# n64-snac.net
KiCad netlist of a schematic drawn in EAGLE
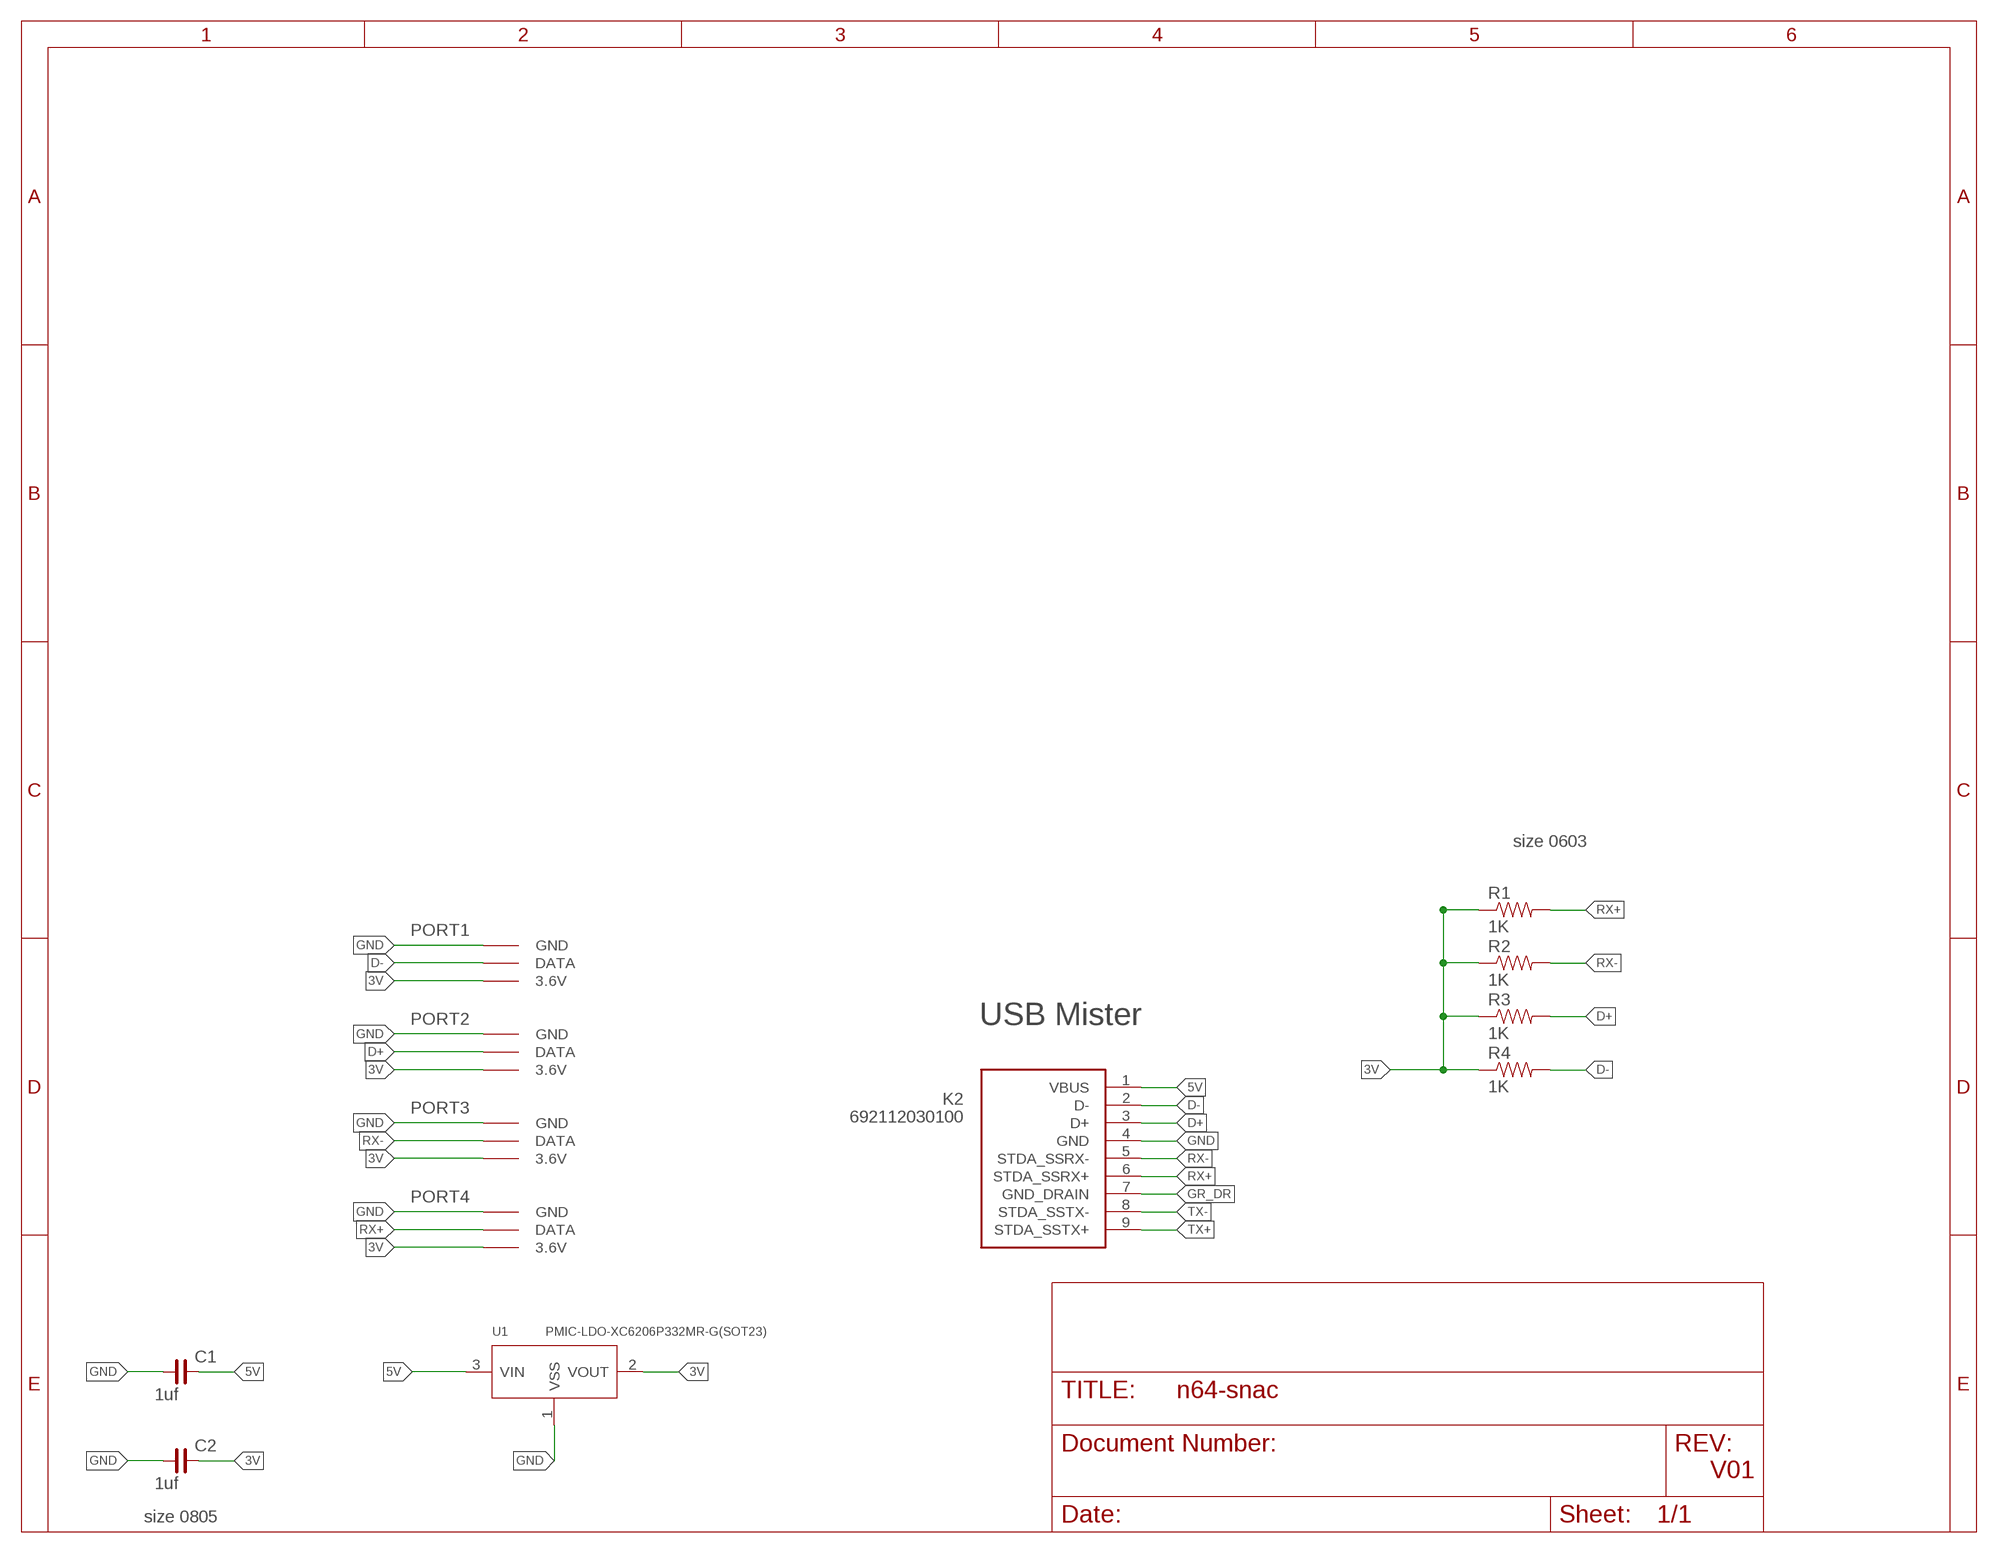
[diagram p0: schematic, sheet 1]

(export (version "E")
  (design (tool "Eeschema 10.0.6"))
  (components
    (comp (ref "C1")
      (value "1uf")
      (footprint "eagle-import:C0805")
      (libsource (lib "eagle-import") (part "C_0805"))
    )
    (comp (ref "C2")
      (value "1uf")
      (footprint "eagle-import:C0805")
      (libsource (lib "eagle-import") (part "C_0805"))
    )
    (comp (ref "K2")
      (value "692112030100")
      (footprint "eagle-import:692112030100")
      (libsource (lib "eagle-import") (part "692112030100"))
    )
    (comp (ref "R1")
      (value "1K")
      (footprint "eagle-import:0603-RES")
      (libsource (lib "eagle-import") (part "RESISTOR0603-RES"))
    )
    (comp (ref "R2")
      (value "1K")
      (footprint "eagle-import:0603-RES")
      (libsource (lib "eagle-import") (part "RESISTOR0603-RES"))
    )
    (comp (ref "R3")
      (value "1K")
      (footprint "eagle-import:0603-RES")
      (libsource (lib "eagle-import") (part "RESISTOR0603-RES"))
    )
    (comp (ref "R4")
      (value "1K")
      (footprint "eagle-import:0603-RES")
      (libsource (lib "eagle-import") (part "RESISTOR0603-RES"))
    )
    (comp (ref "U$1")
      (value "N64CONN")
      (footprint "eagle-import:N64CONN")
      (libsource (lib "eagle-import") (part "N64CONN"))
    )
    (comp (ref "U$2")
      (value "N64CONN")
      (footprint "eagle-import:N64CONN")
      (libsource (lib "eagle-import") (part "N64CONN"))
    )
    (comp (ref "U$3")
      (value "N64CONN")
      (footprint "eagle-import:N64CONN")
      (libsource (lib "eagle-import") (part "N64CONN"))
    )
    (comp (ref "U$4")
      (value "N64CONN")
      (footprint "eagle-import:N64CONN")
      (libsource (lib "eagle-import") (part "N64CONN"))
    )
    (comp (ref "U1")
      (value "PMIC-LDO-XC6206P332MR-G(SOT23)")
      (footprint "eagle-import:SOT-23")
      (fields (field (name "MF") "Torex") (field (name "MP") "XC6206P332MR-G"))
      (libsource (lib "eagle-import") (part "PMIC-LDO-XC6206P332MR-G(SOT23)"))
    )
  )
  (nets
    (net (code "1") (name "3V") (class "Default")
      (node (ref "C2") (pin "2") (pinfunction "2_2") (pintype "passive"))
      (node (ref "R1") (pin "1") (pinfunction "1_1") (pintype "passive"))
      (node (ref "R2") (pin "1") (pinfunction "1_1") (pintype "passive"))
      (node (ref "R3") (pin "1") (pinfunction "1_1") (pintype "passive"))
      (node (ref "R4") (pin "1") (pinfunction "1_1") (pintype "passive"))
      (node (ref "U$1") (pin "3.6V") (pinfunction "3.6V_3.6V") (pintype "power_in"))
      (node (ref "U$2") (pin "3.6V") (pinfunction "3.6V_3.6V") (pintype "power_in"))
      (node (ref "U$3") (pin "3.6V") (pinfunction "3.6V_3.6V") (pintype "power_in"))
      (node (ref "U$4") (pin "3.6V") (pinfunction "3.6V_3.6V") (pintype "power_in"))
      (node (ref "U1") (pin "2") (pinfunction "VOUT_2") (pintype "output"))
    )
    (net (code "2") (name "5V") (class "Default")
      (node (ref "C1") (pin "2") (pinfunction "2_2") (pintype "passive"))
      (node (ref "K2") (pin "1") (pinfunction "VBUS_1") (pintype "bidirectional"))
      (node (ref "U1") (pin "3") (pinfunction "VIN_3") (pintype "input"))
    )
    (net (code "3") (name "D+") (class "Default")
      (node (ref "K2") (pin "3") (pinfunction "D+_3") (pintype "bidirectional"))
      (node (ref "R3") (pin "2") (pinfunction "2_2") (pintype "passive"))
      (node (ref "U$1") (pin "DATA") (pinfunction "DATA_DATA") (pintype "bidirectional"))
    )
    (net (code "4") (name "D-") (class "Default")
      (node (ref "K2") (pin "2") (pinfunction "D-_2") (pintype "bidirectional"))
      (node (ref "R4") (pin "2") (pinfunction "2_2") (pintype "passive"))
      (node (ref "U$3") (pin "DATA") (pinfunction "DATA_DATA") (pintype "bidirectional"))
    )
    (net (code "5") (name "GND") (class "Default")
      (node (ref "C1") (pin "1") (pinfunction "1_1") (pintype "passive"))
      (node (ref "C2") (pin "1") (pinfunction "1_1") (pintype "passive"))
      (node (ref "K2") (pin "4") (pinfunction "GND_4") (pintype "bidirectional"))
      (node (ref "U$1") (pin "GND") (pinfunction "GND_GND") (pintype "input"))
      (node (ref "U$2") (pin "GND") (pinfunction "GND_GND") (pintype "input"))
      (node (ref "U$3") (pin "GND") (pinfunction "GND_GND") (pintype "input"))
      (node (ref "U$4") (pin "GND") (pinfunction "GND_GND") (pintype "input"))
      (node (ref "U1") (pin "1") (pinfunction "VSS_1") (pintype "power_in"))
    )
    (net (code "6") (name "GR_DR") (class "Default")
      (node (ref "K2") (pin "7") (pinfunction "GND_DRAIN_7") (pintype "bidirectional"))
    )
    (net (code "7") (name "RX+") (class "Default")
      (node (ref "K2") (pin "6") (pinfunction "STDA_SSRX+_6") (pintype "bidirectional"))
      (node (ref "R1") (pin "2") (pinfunction "2_2") (pintype "passive"))
      (node (ref "U$4") (pin "DATA") (pinfunction "DATA_DATA") (pintype "bidirectional"))
    )
    (net (code "8") (name "RX-") (class "Default")
      (node (ref "K2") (pin "5") (pinfunction "STDA_SSRX-_5") (pintype "bidirectional"))
      (node (ref "R2") (pin "2") (pinfunction "2_2") (pintype "passive"))
      (node (ref "U$2") (pin "DATA") (pinfunction "DATA_DATA") (pintype "bidirectional"))
    )
    (net (code "9") (name "TX+") (class "Default")
      (node (ref "K2") (pin "9") (pinfunction "STDA_SSTX+_9") (pintype "bidirectional"))
    )
    (net (code "10") (name "TX-") (class "Default")
      (node (ref "K2") (pin "8") (pinfunction "STDA_SSTX-_8") (pintype "bidirectional"))
    )
  )
)
